# SensorShield.net
KiCad netlist of a schematic drawn in EAGLE
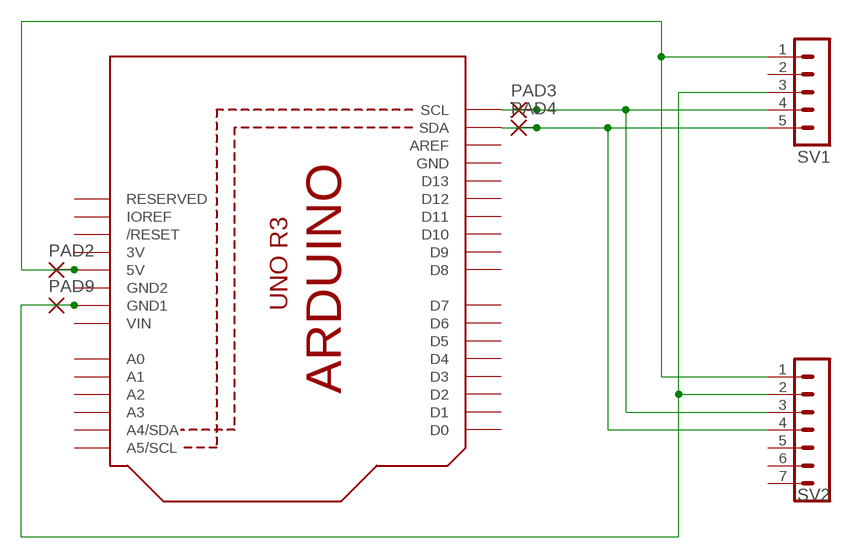
[diagram p0: schematic, sheet 1]

(export (version "E")
  (design (tool "Eeschema 10.0.6"))
  (components
    (comp (ref "PAD2")
      (value "1,6/0,8")
      (footprint "eagle-import:1,6_0,8")
      (libsource (lib "eagle-import") (part "1,6/0,8"))
    )
    (comp (ref "PAD3")
      (value "1,6/0,8")
      (footprint "eagle-import:1,6_0,8")
      (libsource (lib "eagle-import") (part "1,6/0,8"))
    )
    (comp (ref "PAD4")
      (value "1,6/0,8")
      (footprint "eagle-import:1,6_0,8")
      (libsource (lib "eagle-import") (part "1,6/0,8"))
    )
    (comp (ref "PAD9")
      (value "1,6/0,8")
      (footprint "eagle-import:1,6_0,8")
      (libsource (lib "eagle-import") (part "1,6/0,8"))
    )
    (comp (ref "SV1")
      (value "MA05-1")
      (footprint "eagle-import:MA05-1")
      (libsource (lib "eagle-import") (part "MA05-1"))
    )
    (comp (ref "SV2")
      (value "MA07-1")
      (footprint "eagle-import:MA07-1")
      (libsource (lib "eagle-import") (part "MA07-1"))
    )
    (comp (ref "U1")
      (value "ARDUINOR3-BPLACE")
      (footprint "eagle-import:ARDUINOR3-BPLACE")
      (libsource (lib "eagle-import") (part "ARDUINOR3-BPLACE"))
    )
  )
  (nets
    (net (code "1") (name "/3V") (class "Default")
      (node (ref "U1") (pin "3V") (pinfunction "3V_3V") (pintype "power_in"))
    )
    (net (code "2") (name "/GND") (class "Default")
      (node (ref "U1") (pin "GND") (pinfunction "GND_GND") (pintype "power_in"))
    )
    (net (code "3") (name "/GND2") (class "Default")
      (node (ref "U1") (pin "GND2") (pinfunction "GND2_GND2") (pintype "power_in"))
    )
    (net (code "4") (name "/VIN") (class "Default")
      (node (ref "U1") (pin "VIN") (pinfunction "VIN_VIN") (pintype "power_in"))
    )
    (net (code "5") (name "Net-(PAD2-P)") (class "Default")
      (node (ref "PAD2") (pin "1") (pinfunction "P_1") (pintype "passive"))
      (node (ref "SV1") (pin "1") (pinfunction "1_1") (pintype "passive"))
      (node (ref "SV2") (pin "1") (pinfunction "1_1") (pintype "passive"))
      (node (ref "U1") (pin "5V") (pinfunction "5V_5V") (pintype "power_in"))
    )
    (net (code "6") (name "Net-(PAD3-P)") (class "Default")
      (node (ref "PAD3") (pin "1") (pinfunction "P_1") (pintype "passive"))
      (node (ref "SV1") (pin "4") (pinfunction "4_4") (pintype "passive"))
      (node (ref "SV2") (pin "3") (pinfunction "3_3") (pintype "passive"))
      (node (ref "U1") (pin "SCL") (pinfunction "SCL_SCL") (pintype "bidirectional"))
    )
    (net (code "7") (name "Net-(PAD4-P)") (class "Default")
      (node (ref "PAD4") (pin "1") (pinfunction "P_1") (pintype "passive"))
      (node (ref "SV1") (pin "5") (pinfunction "5_5") (pintype "passive"))
      (node (ref "SV2") (pin "4") (pinfunction "4_4") (pintype "passive"))
      (node (ref "U1") (pin "SDA") (pinfunction "SDA_SDA") (pintype "bidirectional"))
    )
    (net (code "8") (name "Net-(PAD9-P)") (class "Default")
      (node (ref "PAD9") (pin "1") (pinfunction "P_1") (pintype "passive"))
      (node (ref "SV1") (pin "3") (pinfunction "3_3") (pintype "passive"))
      (node (ref "SV2") (pin "2") (pinfunction "2_2") (pintype "passive"))
      (node (ref "U1") (pin "GND1") (pinfunction "GND1_GND1") (pintype "power_in"))
    )
    (net (code "9") (name "unconnected-(SV1-Pad2)") (class "Default")
      (node (ref "SV1") (pin "2") (pinfunction "2_2") (pintype "passive"))
    )
    (net (code "10") (name "unconnected-(SV2-Pad5)") (class "Default")
      (node (ref "SV2") (pin "5") (pinfunction "5_5") (pintype "passive"))
    )
    (net (code "11") (name "unconnected-(SV2-Pad6)") (class "Default")
      (node (ref "SV2") (pin "6") (pinfunction "6_6") (pintype "passive"))
    )
    (net (code "12") (name "unconnected-(SV2-Pad7)") (class "Default")
      (node (ref "SV2") (pin "7") (pinfunction "7_7") (pintype "passive"))
    )
    (net (code "13") (name "unconnected-(U1-A4{slash}SDA-PadA4)") (class "Default")
      (node (ref "U1") (pin "A4") (pinfunction "A4/SDA_A4") (pintype "bidirectional"))
    )
    (net (code "14") (name "unconnected-(U1-A5{slash}SCL-PadA5)") (class "Default")
      (node (ref "U1") (pin "A5") (pinfunction "A5/SCL_A5") (pintype "bidirectional"))
    )
    (net (code "15") (name "unconnected-(U1-PadA0)") (class "Default")
      (node (ref "U1") (pin "A0") (pinfunction "A0_A0") (pintype "bidirectional"))
    )
    (net (code "16") (name "unconnected-(U1-PadA1)") (class "Default")
      (node (ref "U1") (pin "A1") (pinfunction "A1_A1") (pintype "bidirectional"))
    )
    (net (code "17") (name "unconnected-(U1-PadA2)") (class "Default")
      (node (ref "U1") (pin "A2") (pinfunction "A2_A2") (pintype "bidirectional"))
    )
    (net (code "18") (name "unconnected-(U1-PadA3)") (class "Default")
      (node (ref "U1") (pin "A3") (pinfunction "A3_A3") (pintype "bidirectional"))
    )
    (net (code "19") (name "unconnected-(U1-PadAREF)") (class "Default")
      (node (ref "U1") (pin "AREF") (pinfunction "AREF_AREF") (pintype "bidirectional"))
    )
    (net (code "20") (name "unconnected-(U1-PadD0)") (class "Default")
      (node (ref "U1") (pin "D0") (pinfunction "D0_D0") (pintype "bidirectional"))
    )
    (net (code "21") (name "unconnected-(U1-PadD1)") (class "Default")
      (node (ref "U1") (pin "D1") (pinfunction "D1_D1") (pintype "bidirectional"))
    )
    (net (code "22") (name "unconnected-(U1-PadD2)") (class "Default")
      (node (ref "U1") (pin "D2") (pinfunction "D2_D2") (pintype "bidirectional"))
    )
    (net (code "23") (name "unconnected-(U1-PadD3)") (class "Default")
      (node (ref "U1") (pin "D3") (pinfunction "D3_D3") (pintype "bidirectional"))
    )
    (net (code "24") (name "unconnected-(U1-PadD4)") (class "Default")
      (node (ref "U1") (pin "D4") (pinfunction "D4_D4") (pintype "bidirectional"))
    )
    (net (code "25") (name "unconnected-(U1-PadD5)") (class "Default")
      (node (ref "U1") (pin "D5") (pinfunction "D5_D5") (pintype "bidirectional"))
    )
    (net (code "26") (name "unconnected-(U1-PadD6)") (class "Default")
      (node (ref "U1") (pin "D6") (pinfunction "D6_D6") (pintype "bidirectional"))
    )
    (net (code "27") (name "unconnected-(U1-PadD7)") (class "Default")
      (node (ref "U1") (pin "D7") (pinfunction "D7_D7") (pintype "bidirectional"))
    )
    (net (code "28") (name "unconnected-(U1-PadD8)") (class "Default")
      (node (ref "U1") (pin "D8") (pinfunction "D8_D8") (pintype "bidirectional"))
    )
    (net (code "29") (name "unconnected-(U1-PadD9)") (class "Default")
      (node (ref "U1") (pin "D9") (pinfunction "D9_D9") (pintype "bidirectional"))
    )
    (net (code "30") (name "unconnected-(U1-PadD10)") (class "Default")
      (node (ref "U1") (pin "D10") (pinfunction "D10_D10") (pintype "bidirectional"))
    )
    (net (code "31") (name "unconnected-(U1-PadD11)") (class "Default")
      (node (ref "U1") (pin "D11") (pinfunction "D11_D11") (pintype "bidirectional"))
    )
    (net (code "32") (name "unconnected-(U1-PadD12)") (class "Default")
      (node (ref "U1") (pin "D12") (pinfunction "D12_D12") (pintype "bidirectional"))
    )
    (net (code "33") (name "unconnected-(U1-PadD13)") (class "Default")
      (node (ref "U1") (pin "D13") (pinfunction "D13_D13") (pintype "bidirectional"))
    )
    (net (code "34") (name "unconnected-(U1-PadIOREF)") (class "Default")
      (node (ref "U1") (pin "IOREF") (pinfunction "IOREF_IOREF") (pintype "output"))
    )
    (net (code "35") (name "unconnected-(U1-PadRESERVED)") (class "Default")
      (node (ref "U1") (pin "RESERVED") (pinfunction "RESERVED_RESERVED") (pintype "no_connect"))
    )
    (net (code "36") (name "unconnected-(U1-{slash}RESET-PadRESET)") (class "Default")
      (node (ref "U1") (pin "RESET") (pinfunction "/RESET_RESET") (pintype "bidirectional"))
    )
  )
)
